# ADXL345_Breakout.net
KiCad netlist of a schematic drawn in EAGLE
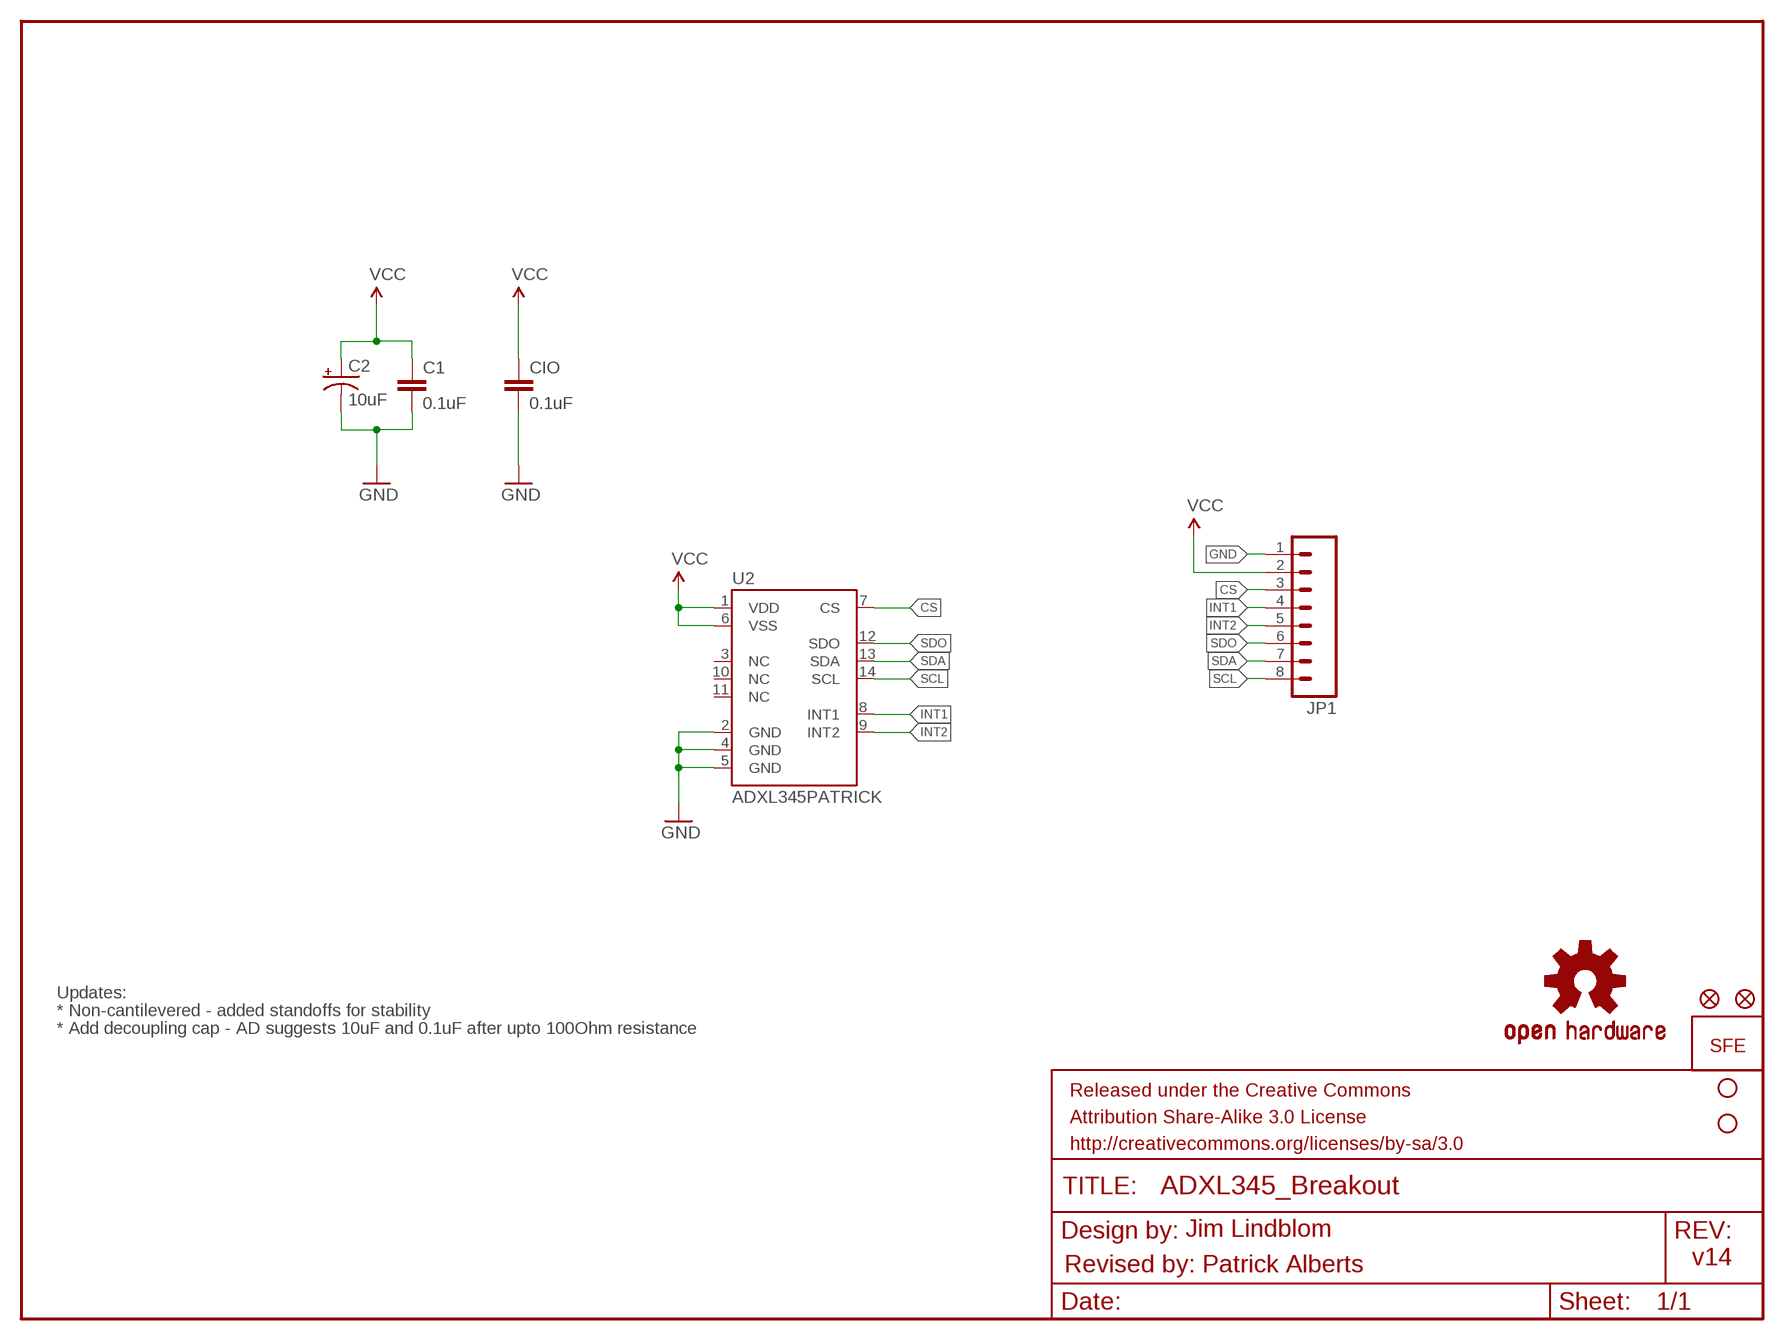
[diagram p0: schematic, sheet 1]

(export (version "E")
  (design (tool "Eeschema 10.0.6"))
  (components
    (comp (ref "C1")
      (value "0.1uF")
      (footprint "eagle-import:0603-CAP")
      (libsource (lib "eagle-import") (part "CAP0603-CAP"))
    )
    (comp (ref "C2")
      (value "10uF")
      (footprint "eagle-import:EIA3216")
      (libsource (lib "eagle-import") (part "CAP_POL1206"))
    )
    (comp (ref "CIO")
      (value "0.1uF")
      (footprint "eagle-import:0603-CAP")
      (libsource (lib "eagle-import") (part "CAP0603-CAP"))
    )
    (comp (ref "JP1")
      (value "M08")
      (footprint "eagle-import:1X08")
      (libsource (lib "eagle-import") (part "M08"))
    )
    (comp (ref "JP2")
      (value "STAND-OFF")
      (footprint "eagle-import:STAND-OFF")
      (libsource (lib "eagle-import") (part "STAND-OFF"))
    )
    (comp (ref "JP3")
      (value "STAND-OFF")
      (footprint "eagle-import:STAND-OFF")
      (libsource (lib "eagle-import") (part "STAND-OFF"))
    )
    (comp (ref "JP4")
      (value "FIDUCIAL1X2")
      (footprint "eagle-import:FIDUCIAL-1X2")
      (libsource (lib "eagle-import") (part "FIDUCIAL1X2"))
    )
    (comp (ref "JP5")
      (value "FIDUCIAL1X2")
      (footprint "eagle-import:FIDUCIAL-1X2")
      (libsource (lib "eagle-import") (part "FIDUCIAL1X2"))
    )
    (comp (ref "U$2")
      (value "LOGO-SFENEW")
      (footprint "eagle-import:SFE-NEW-WEBLOGO")
      (libsource (lib "eagle-import") (part "LOGO-SFENEW"))
    )
    (comp (ref "U$3")
      (value "OSHW-LOGOS")
      (footprint "eagle-import:OSHW-LOGO-S")
      (libsource (lib "eagle-import") (part "OSHW-LOGOS"))
    )
    (comp (ref "U2")
      (value "ADXL345PATRICK")
      (footprint "eagle-import:LGA14_1_1_PATRICK")
      (libsource (lib "eagle-import") (part "ADXL345PATRICK"))
    )
  )
  (nets
    (net (code "1") (name "CS") (class "Default")
      (node (ref "JP1") (pin "3") (pinfunction "3_3") (pintype "passive"))
      (node (ref "U2") (pin "7") (pinfunction "CS_7") (pintype "bidirectional"))
    )
    (net (code "2") (name "GND") (class "Default")
      (node (ref "C1") (pin "2") (pinfunction "2_2") (pintype "passive"))
      (node (ref "C2") (pin "C") (pinfunction "-_C") (pintype "passive"))
      (node (ref "CIO") (pin "2") (pinfunction "2_2") (pintype "passive"))
      (node (ref "JP1") (pin "1") (pinfunction "1_1") (pintype "passive"))
      (node (ref "U2") (pin "2") (pinfunction "GND_2") (pintype "bidirectional"))
      (node (ref "U2") (pin "4") (pinfunction "GND_4") (pintype "bidirectional"))
      (node (ref "U2") (pin "5") (pinfunction "GND_5") (pintype "bidirectional"))
    )
    (net (code "3") (name "INT1") (class "Default")
      (node (ref "JP1") (pin "4") (pinfunction "4_4") (pintype "passive"))
      (node (ref "U2") (pin "8") (pinfunction "INT1_8") (pintype "bidirectional"))
    )
    (net (code "4") (name "INT2") (class "Default")
      (node (ref "JP1") (pin "5") (pinfunction "5_5") (pintype "passive"))
      (node (ref "U2") (pin "9") (pinfunction "INT2_9") (pintype "bidirectional"))
    )
    (net (code "5") (name "SCL") (class "Default")
      (node (ref "JP1") (pin "8") (pinfunction "8_8") (pintype "passive"))
      (node (ref "U2") (pin "14") (pinfunction "SCL_14") (pintype "bidirectional"))
    )
    (net (code "6") (name "SDA") (class "Default")
      (node (ref "JP1") (pin "7") (pinfunction "7_7") (pintype "passive"))
      (node (ref "U2") (pin "13") (pinfunction "SDA_13") (pintype "bidirectional"))
    )
    (net (code "7") (name "SDO") (class "Default")
      (node (ref "JP1") (pin "6") (pinfunction "6_6") (pintype "passive"))
      (node (ref "U2") (pin "12") (pinfunction "SDO_12") (pintype "bidirectional"))
    )
    (net (code "8") (name "VCC") (class "Default")
      (node (ref "C1") (pin "1") (pinfunction "1_1") (pintype "passive"))
      (node (ref "C2") (pin "A") (pinfunction "+_A") (pintype "passive"))
      (node (ref "CIO") (pin "1") (pinfunction "1_1") (pintype "passive"))
      (node (ref "JP1") (pin "2") (pinfunction "2_2") (pintype "passive"))
      (node (ref "U2") (pin "1") (pinfunction "VDD_1") (pintype "bidirectional"))
      (node (ref "U2") (pin "6") (pinfunction "VSS_6") (pintype "bidirectional"))
    )
    (net (code "9") (name "unconnected-(U2-NC-Pad3)") (class "Default")
      (node (ref "U2") (pin "3") (pinfunction "NC_3") (pintype "bidirectional"))
    )
    (net (code "10") (name "unconnected-(U2-NC-Pad10)") (class "Default")
      (node (ref "U2") (pin "10") (pinfunction "NC_10") (pintype "bidirectional"))
    )
    (net (code "11") (name "unconnected-(U2-NC-Pad11)") (class "Default")
      (node (ref "U2") (pin "11") (pinfunction "NC_11") (pintype "bidirectional"))
    )
  )
)
